# Startgate_Controller-Mainboard.net
KiCad netlist of a schematic drawn in EAGLE
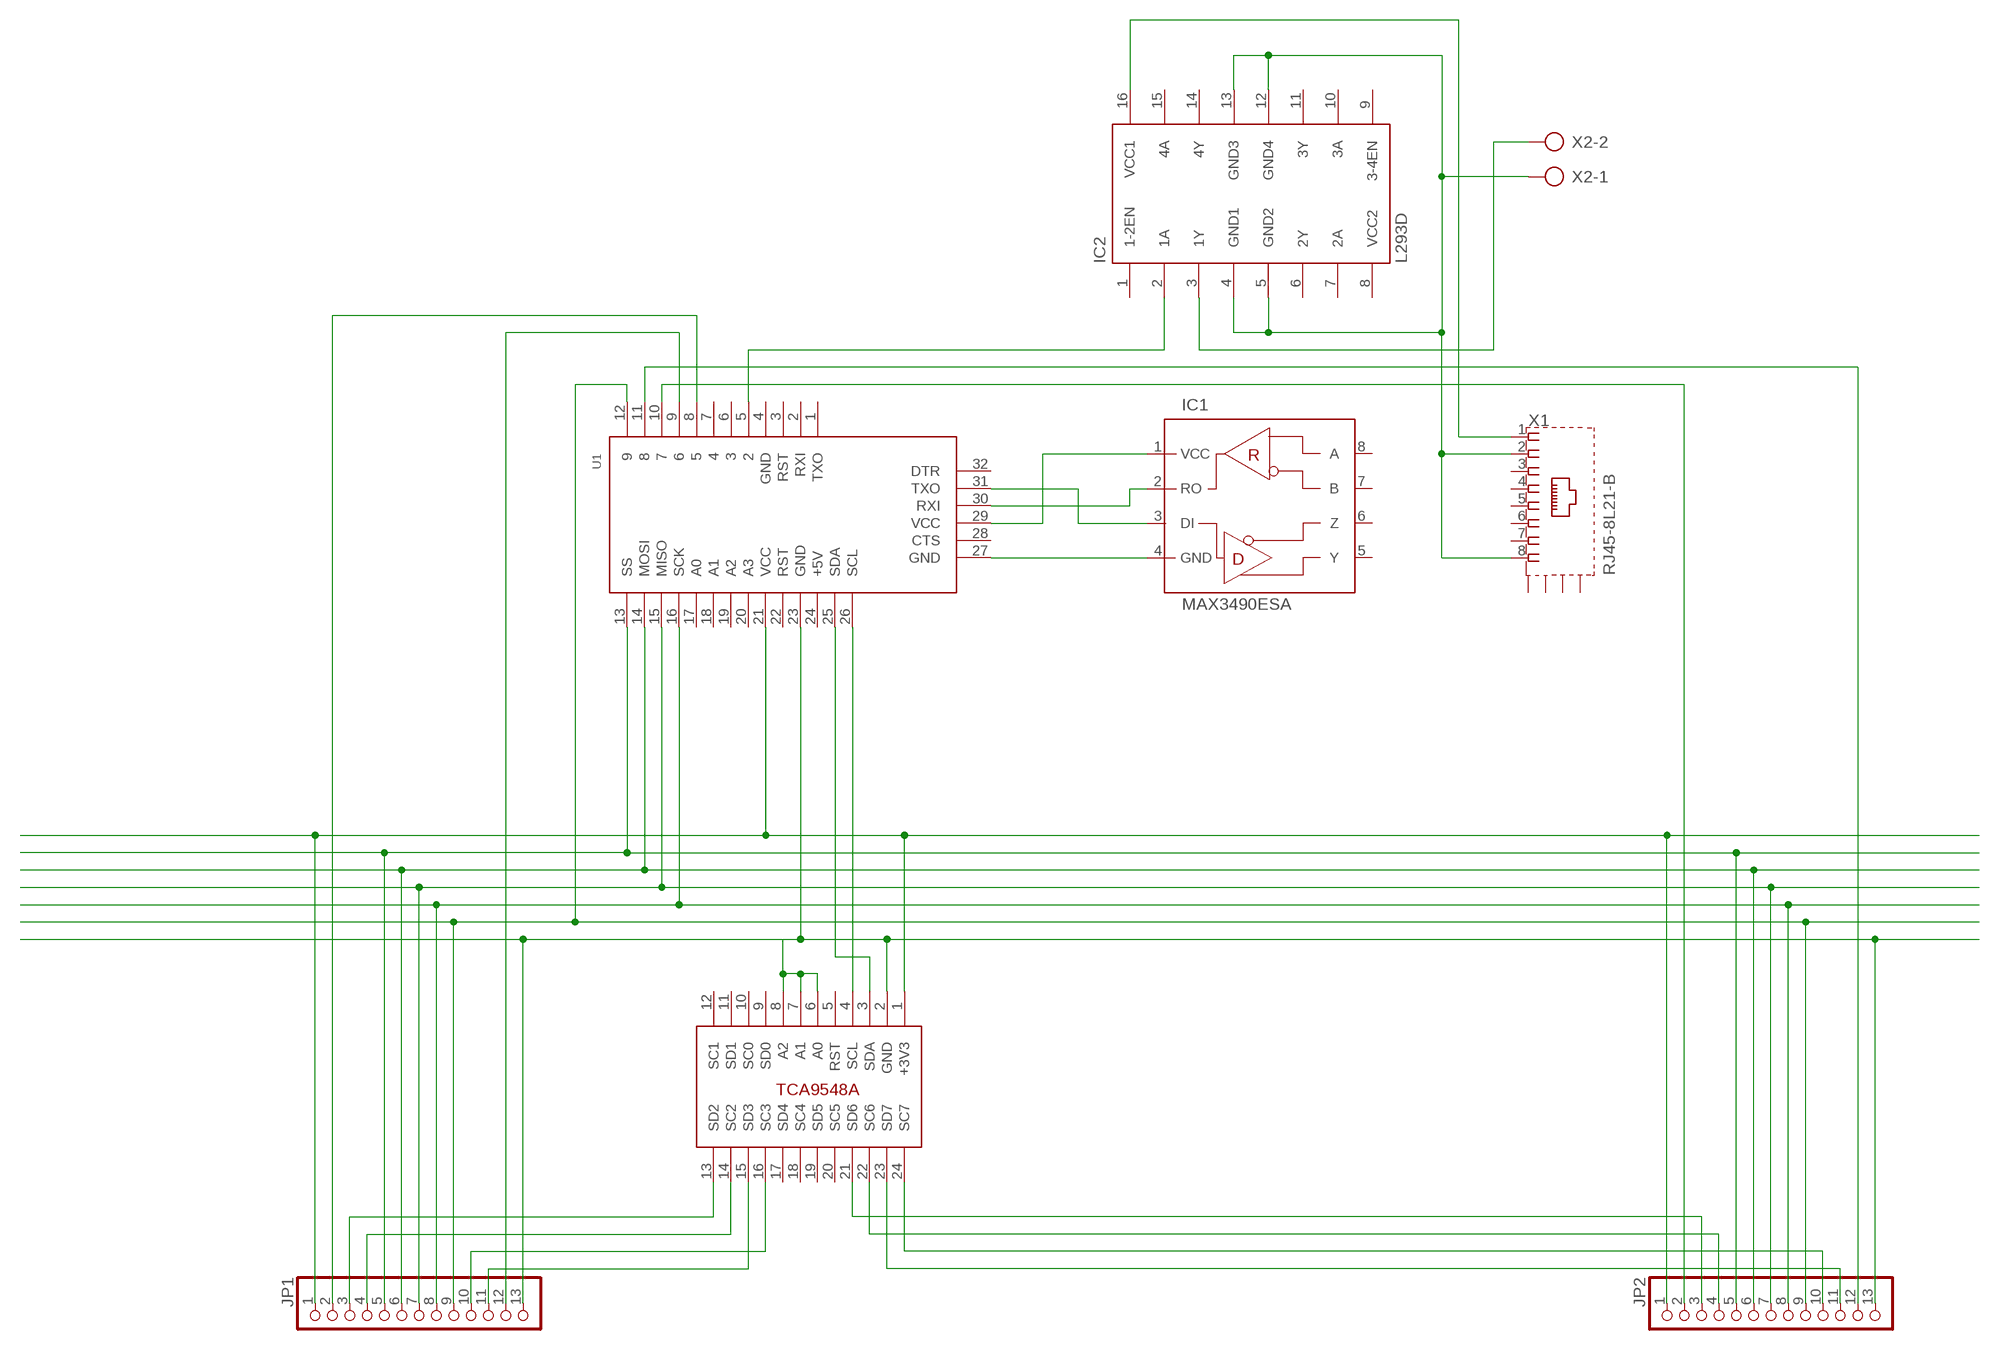
[diagram p0: schematic, sheet 1]

(export (version "E")
  (design (tool "Eeschema 10.0.6"))
  (components
    (comp (ref "IC1")
      (value "MAX3490ESA")
      (footprint "eagle-import:SO08")
      (libsource (lib "eagle-import") (part "MAX3490ESA"))
    )
    (comp (ref "IC2")
      (value "L293D")
      (footprint "eagle-import:DIL16")
      (libsource (lib "eagle-import") (part "L293D"))
    )
    (comp (ref "JP1")
      (value "PINHD-1X13")
      (footprint "eagle-import:1X13")
      (libsource (lib "eagle-import") (part "PINHD-1X13"))
    )
    (comp (ref "JP2")
      (value "PINHD-1X13")
      (footprint "eagle-import:1X13")
      (libsource (lib "eagle-import") (part "PINHD-1X13"))
    )
    (comp (ref "U$1")
      (value "TCA9548A")
      (footprint "eagle-import:DIL24")
      (libsource (lib "eagle-import") (part "TCA9548A"))
    )
    (comp (ref "U1")
      (value "ARDUINOPROMINI")
      (footprint "eagle-import:ARDUINOPROMINI")
      (libsource (lib "eagle-import") (part "ARDUINOPROMINI"))
    )
    (comp (ref "X1")
      (value "RJ45-8L21-B")
      (footprint "eagle-import:RJ45-SHIELD1")
      (libsource (lib "eagle-import") (part "RJ4521-B-8L"))
    )
    (comp (ref "X2")
      (value "AK300/2")
      (footprint "eagle-import:AK300_2")
      (libsource (lib "eagle-import") (part "AK300/2"))
    )
  )
  (nets
    (net (code "1") (name "/+3V3") (class "Default")
      (node (ref "IC1") (pin "1") (pinfunction "VCC_1") (pintype "power_in"))
      (node (ref "JP1") (pin "1") (pinfunction "1_1") (pintype "passive"))
      (node (ref "JP2") (pin "1") (pinfunction "1_1") (pintype "passive"))
      (node (ref "U$1") (pin "1") (pinfunction "+3V3_1") (pintype "power_in"))
      (node (ref "U1") (pin "21") (pinfunction "VCC_21") (pintype "bidirectional"))
      (node (ref "U1") (pin "29") (pinfunction "VCC_29") (pintype "bidirectional"))
    )
    (net (code "2") (name "/+5V") (class "Default")
      (node (ref "U1") (pin "24") (pinfunction "+5V_24") (pintype "power_in"))
    )
    (net (code "3") (name "/GND") (class "Default")
      (node (ref "IC1") (pin "4") (pinfunction "GND_4") (pintype "power_in"))
      (node (ref "JP1") (pin "13") (pinfunction "13_13") (pintype "passive"))
      (node (ref "JP2") (pin "13") (pinfunction "13_13") (pintype "passive"))
      (node (ref "U$1") (pin "2") (pinfunction "GND_2") (pintype "power_in"))
      (node (ref "U$1") (pin "6") (pinfunction "A0_6") (pintype "bidirectional"))
      (node (ref "U$1") (pin "7") (pinfunction "A1_7") (pintype "bidirectional"))
      (node (ref "U$1") (pin "8") (pinfunction "A2_8") (pintype "bidirectional"))
      (node (ref "U1") (pin "23") (pinfunction "GND_23") (pintype "bidirectional"))
      (node (ref "U1") (pin "27") (pinfunction "GND_27") (pintype "bidirectional"))
    )
    (net (code "4") (name "/VCC2") (class "Default")
      (node (ref "IC2") (pin "8") (pinfunction "VCC2_8") (pintype "power_in"))
    )
    (net (code "5") (name "Net-(IC1-DI)") (class "Default")
      (node (ref "IC1") (pin "3") (pinfunction "DI_3") (pintype "input"))
      (node (ref "U1") (pin "31") (pinfunction "TXO_31") (pintype "bidirectional"))
    )
    (net (code "6") (name "Net-(IC1-RO)") (class "Default")
      (node (ref "IC1") (pin "2") (pinfunction "RO_2") (pintype "output"))
      (node (ref "U1") (pin "30") (pinfunction "RXI_30") (pintype "bidirectional"))
    )
    (net (code "7") (name "Net-(IC2-1A)") (class "Default")
      (node (ref "IC2") (pin "2") (pinfunction "1A_2") (pintype "input"))
      (node (ref "U1") (pin "5") (pinfunction "2_5") (pintype "bidirectional"))
    )
    (net (code "8") (name "Net-(IC2-1Y)") (class "Default")
      (node (ref "IC2") (pin "3") (pinfunction "1Y_3") (pintype "output"))
      (node (ref "X2") (pin "2") (pinfunction "KL_2") (pintype "passive"))
    )
    (net (code "9") (name "Net-(IC2-GND1)") (class "Default")
      (node (ref "IC2") (pin "12") (pinfunction "GND4_12") (pintype "power_in"))
      (node (ref "IC2") (pin "13") (pinfunction "GND3_13") (pintype "power_in"))
      (node (ref "IC2") (pin "4") (pinfunction "GND1_4") (pintype "power_in"))
      (node (ref "IC2") (pin "5") (pinfunction "GND2_5") (pintype "power_in"))
      (node (ref "X1") (pin "2") (pinfunction "2_2") (pintype "passive"))
      (node (ref "X1") (pin "8") (pinfunction "8_8") (pintype "passive"))
      (node (ref "X2") (pin "1") (pinfunction "KL_1") (pintype "passive"))
    )
    (net (code "10") (name "Net-(IC2-VCC1)") (class "Default")
      (node (ref "IC2") (pin "16") (pinfunction "VCC1_16") (pintype "power_in"))
      (node (ref "X1") (pin "1") (pinfunction "1_1") (pintype "passive"))
    )
    (net (code "11") (name "Net-(U$1-SC2)") (class "Default")
      (node (ref "JP1") (pin "4") (pinfunction "4_4") (pintype "passive"))
      (node (ref "U$1") (pin "14") (pinfunction "SC2_14") (pintype "bidirectional"))
    )
    (net (code "12") (name "Net-(U$1-SC3)") (class "Default")
      (node (ref "JP1") (pin "10") (pinfunction "10_10") (pintype "passive"))
      (node (ref "U$1") (pin "16") (pinfunction "SC3_16") (pintype "bidirectional"))
    )
    (net (code "13") (name "Net-(U$1-SC6)") (class "Default")
      (node (ref "JP2") (pin "4") (pinfunction "4_4") (pintype "passive"))
      (node (ref "U$1") (pin "22") (pinfunction "SC6_22") (pintype "bidirectional"))
    )
    (net (code "14") (name "Net-(U$1-SC7)") (class "Default")
      (node (ref "JP2") (pin "10") (pinfunction "10_10") (pintype "passive"))
      (node (ref "U$1") (pin "24") (pinfunction "SC7_24") (pintype "bidirectional"))
    )
    (net (code "15") (name "Net-(U$1-SCL)") (class "Default")
      (node (ref "U$1") (pin "4") (pinfunction "SCL_4") (pintype "bidirectional"))
      (node (ref "U1") (pin "26") (pinfunction "SCL_26") (pintype "bidirectional"))
    )
    (net (code "16") (name "Net-(U$1-SD2)") (class "Default")
      (node (ref "JP1") (pin "3") (pinfunction "3_3") (pintype "passive"))
      (node (ref "U$1") (pin "13") (pinfunction "SD2_13") (pintype "bidirectional"))
    )
    (net (code "17") (name "Net-(U$1-SD3)") (class "Default")
      (node (ref "JP1") (pin "11") (pinfunction "11_11") (pintype "passive"))
      (node (ref "U$1") (pin "15") (pinfunction "SD3_15") (pintype "bidirectional"))
    )
    (net (code "18") (name "Net-(U$1-SD6)") (class "Default")
      (node (ref "JP2") (pin "3") (pinfunction "3_3") (pintype "passive"))
      (node (ref "U$1") (pin "21") (pinfunction "SD6_21") (pintype "bidirectional"))
    )
    (net (code "19") (name "Net-(U$1-SD7)") (class "Default")
      (node (ref "JP2") (pin "11") (pinfunction "11_11") (pintype "passive"))
      (node (ref "U$1") (pin "23") (pinfunction "SD7_23") (pintype "bidirectional"))
    )
    (net (code "20") (name "Net-(U$1-SDA)") (class "Default")
      (node (ref "U$1") (pin "3") (pinfunction "SDA_3") (pintype "bidirectional"))
      (node (ref "U1") (pin "25") (pinfunction "SDA_25") (pintype "bidirectional"))
    )
    (net (code "21") (name "Net-(U1-5)") (class "Default")
      (node (ref "JP1") (pin "2") (pinfunction "2_2") (pintype "passive"))
      (node (ref "U1") (pin "8") (pinfunction "5_8") (pintype "bidirectional"))
    )
    (net (code "22") (name "Net-(U1-6)") (class "Default")
      (node (ref "JP1") (pin "12") (pinfunction "12_12") (pintype "passive"))
      (node (ref "U1") (pin "9") (pinfunction "6_9") (pintype "bidirectional"))
    )
    (net (code "23") (name "Net-(U1-7)") (class "Default")
      (node (ref "JP2") (pin "2") (pinfunction "2_2") (pintype "passive"))
      (node (ref "U1") (pin "10") (pinfunction "7_10") (pintype "bidirectional"))
    )
    (net (code "24") (name "Net-(U1-8)") (class "Default")
      (node (ref "JP2") (pin "12") (pinfunction "12_12") (pintype "passive"))
      (node (ref "U1") (pin "11") (pinfunction "8_11") (pintype "bidirectional"))
    )
    (net (code "25") (name "Net-(U1-9)") (class "Default")
      (node (ref "JP1") (pin "9") (pinfunction "9_9") (pintype "passive"))
      (node (ref "JP2") (pin "9") (pinfunction "9_9") (pintype "passive"))
      (node (ref "U1") (pin "12") (pinfunction "9_12") (pintype "bidirectional"))
    )
    (net (code "26") (name "Net-(U1-MISO)") (class "Default")
      (node (ref "JP1") (pin "7") (pinfunction "7_7") (pintype "passive"))
      (node (ref "JP2") (pin "7") (pinfunction "7_7") (pintype "passive"))
      (node (ref "U1") (pin "15") (pinfunction "MISO_15") (pintype "bidirectional"))
    )
    (net (code "27") (name "Net-(U1-MOSI)") (class "Default")
      (node (ref "JP1") (pin "6") (pinfunction "6_6") (pintype "passive"))
      (node (ref "JP2") (pin "6") (pinfunction "6_6") (pintype "passive"))
      (node (ref "U1") (pin "14") (pinfunction "MOSI_14") (pintype "bidirectional"))
    )
    (net (code "28") (name "Net-(U1-SCK)") (class "Default")
      (node (ref "JP1") (pin "8") (pinfunction "8_8") (pintype "passive"))
      (node (ref "JP2") (pin "8") (pinfunction "8_8") (pintype "passive"))
      (node (ref "U1") (pin "16") (pinfunction "SCK_16") (pintype "bidirectional"))
    )
    (net (code "29") (name "Net-(U1-SS)") (class "Default")
      (node (ref "JP1") (pin "5") (pinfunction "5_5") (pintype "passive"))
      (node (ref "JP2") (pin "5") (pinfunction "5_5") (pintype "passive"))
      (node (ref "U1") (pin "13") (pinfunction "SS_13") (pintype "bidirectional"))
    )
    (net (code "30") (name "unconnected-(IC1-A-Pad8)") (class "Default")
      (node (ref "IC1") (pin "8") (pinfunction "A_8") (pintype "input"))
    )
    (net (code "31") (name "unconnected-(IC1-B-Pad7)") (class "Default")
      (node (ref "IC1") (pin "7") (pinfunction "B_7") (pintype "input"))
    )
    (net (code "32") (name "unconnected-(IC1-Y-Pad5)") (class "Default")
      (node (ref "IC1") (pin "5") (pinfunction "Y_5") (pintype "output"))
    )
    (net (code "33") (name "unconnected-(IC1-Z-Pad6)") (class "Default")
      (node (ref "IC1") (pin "6") (pinfunction "Z_6") (pintype "output"))
    )
    (net (code "34") (name "unconnected-(IC2-1-2EN-Pad1)") (class "Default")
      (node (ref "IC2") (pin "1") (pinfunction "1-2EN_1") (pintype "input"))
    )
    (net (code "35") (name "unconnected-(IC2-2A-Pad7)") (class "Default")
      (node (ref "IC2") (pin "7") (pinfunction "2A_7") (pintype "input"))
    )
    (net (code "36") (name "unconnected-(IC2-2Y-Pad6)") (class "Default")
      (node (ref "IC2") (pin "6") (pinfunction "2Y_6") (pintype "output"))
    )
    (net (code "37") (name "unconnected-(IC2-3-4EN-Pad9)") (class "Default")
      (node (ref "IC2") (pin "9") (pinfunction "3-4EN_9") (pintype "input"))
    )
    (net (code "38") (name "unconnected-(IC2-3A-Pad10)") (class "Default")
      (node (ref "IC2") (pin "10") (pinfunction "3A_10") (pintype "input"))
    )
    (net (code "39") (name "unconnected-(IC2-3Y-Pad11)") (class "Default")
      (node (ref "IC2") (pin "11") (pinfunction "3Y_11") (pintype "output"))
    )
    (net (code "40") (name "unconnected-(IC2-4A-Pad15)") (class "Default")
      (node (ref "IC2") (pin "15") (pinfunction "4A_15") (pintype "input"))
    )
    (net (code "41") (name "unconnected-(IC2-4Y-Pad14)") (class "Default")
      (node (ref "IC2") (pin "14") (pinfunction "4Y_14") (pintype "output"))
    )
    (net (code "42") (name "unconnected-(U$1-RST-Pad5)") (class "Default")
      (node (ref "U$1") (pin "5") (pinfunction "RST_5") (pintype "bidirectional"))
    )
    (net (code "43") (name "unconnected-(U$1-SC0-Pad10)") (class "Default")
      (node (ref "U$1") (pin "10") (pinfunction "SC0_10") (pintype "bidirectional"))
    )
    (net (code "44") (name "unconnected-(U$1-SC1-Pad12)") (class "Default")
      (node (ref "U$1") (pin "12") (pinfunction "SC1_12") (pintype "bidirectional"))
    )
    (net (code "45") (name "unconnected-(U$1-SC4-Pad18)") (class "Default")
      (node (ref "U$1") (pin "18") (pinfunction "SC4_18") (pintype "bidirectional"))
    )
    (net (code "46") (name "unconnected-(U$1-SC5-Pad20)") (class "Default")
      (node (ref "U$1") (pin "20") (pinfunction "SC5_20") (pintype "bidirectional"))
    )
    (net (code "47") (name "unconnected-(U$1-SD0-Pad9)") (class "Default")
      (node (ref "U$1") (pin "9") (pinfunction "SD0_9") (pintype "bidirectional"))
    )
    (net (code "48") (name "unconnected-(U$1-SD1-Pad11)") (class "Default")
      (node (ref "U$1") (pin "11") (pinfunction "SD1_11") (pintype "bidirectional"))
    )
    (net (code "49") (name "unconnected-(U$1-SD4-Pad17)") (class "Default")
      (node (ref "U$1") (pin "17") (pinfunction "SD4_17") (pintype "bidirectional"))
    )
    (net (code "50") (name "unconnected-(U$1-SD5-Pad19)") (class "Default")
      (node (ref "U$1") (pin "19") (pinfunction "SD5_19") (pintype "bidirectional"))
    )
    (net (code "51") (name "unconnected-(U1-3-Pad6)") (class "Default")
      (node (ref "U1") (pin "6") (pinfunction "3_6") (pintype "bidirectional"))
    )
    (net (code "52") (name "unconnected-(U1-4-Pad7)") (class "Default")
      (node (ref "U1") (pin "7") (pinfunction "4_7") (pintype "bidirectional"))
    )
    (net (code "53") (name "unconnected-(U1-A0-Pad17)") (class "Default")
      (node (ref "U1") (pin "17") (pinfunction "A0_17") (pintype "bidirectional"))
    )
    (net (code "54") (name "unconnected-(U1-A1-Pad18)") (class "Default")
      (node (ref "U1") (pin "18") (pinfunction "A1_18") (pintype "bidirectional"))
    )
    (net (code "55") (name "unconnected-(U1-A2-Pad19)") (class "Default")
      (node (ref "U1") (pin "19") (pinfunction "A2_19") (pintype "bidirectional"))
    )
    (net (code "56") (name "unconnected-(U1-A3-Pad20)") (class "Default")
      (node (ref "U1") (pin "20") (pinfunction "A3_20") (pintype "bidirectional"))
    )
    (net (code "57") (name "unconnected-(U1-CTS-Pad28)") (class "Default")
      (node (ref "U1") (pin "28") (pinfunction "CTS_28") (pintype "bidirectional"))
    )
    (net (code "58") (name "unconnected-(U1-DTR-Pad32)") (class "Default")
      (node (ref "U1") (pin "32") (pinfunction "DTR_32") (pintype "bidirectional"))
    )
    (net (code "59") (name "unconnected-(U1-GND-Pad4)") (class "Default")
      (node (ref "U1") (pin "4") (pinfunction "GND_4") (pintype "bidirectional"))
    )
    (net (code "60") (name "unconnected-(U1-RST-Pad3)") (class "Default")
      (node (ref "U1") (pin "3") (pinfunction "RST_3") (pintype "bidirectional"))
    )
    (net (code "61") (name "unconnected-(U1-RST-Pad22)") (class "Default")
      (node (ref "U1") (pin "22") (pinfunction "RST_22") (pintype "bidirectional"))
    )
    (net (code "62") (name "unconnected-(U1-RXI-Pad2)") (class "Default")
      (node (ref "U1") (pin "2") (pinfunction "RXI_2") (pintype "bidirectional"))
    )
    (net (code "63") (name "unconnected-(U1-TXO-Pad1)") (class "Default")
      (node (ref "U1") (pin "1") (pinfunction "TXO_1") (pintype "bidirectional"))
    )
    (net (code "64") (name "unconnected-(X1-Pad3)") (class "Default")
      (node (ref "X1") (pin "3") (pinfunction "3_3") (pintype "passive"))
    )
    (net (code "65") (name "unconnected-(X1-Pad4)") (class "Default")
      (node (ref "X1") (pin "4") (pinfunction "4_4") (pintype "passive"))
    )
    (net (code "66") (name "unconnected-(X1-Pad5)") (class "Default")
      (node (ref "X1") (pin "5") (pinfunction "5_5") (pintype "passive"))
    )
    (net (code "67") (name "unconnected-(X1-Pad6)") (class "Default")
      (node (ref "X1") (pin "6") (pinfunction "6_6") (pintype "passive"))
    )
    (net (code "68") (name "unconnected-(X1-Pad7)") (class "Default")
      (node (ref "X1") (pin "7") (pinfunction "7_7") (pintype "passive"))
    )
    (net (code "69") (name "unconnected-(X1-S-PadS1)") (class "Default")
      (node (ref "X1") (pin "S1") (pinfunction "S_S1") (pintype "passive"))
    )
    (net (code "70") (name "unconnected-(X1-S-PadS2)") (class "Default")
      (node (ref "X1") (pin "S2") (pinfunction "S_S2") (pintype "passive"))
    )
    (net (code "71") (name "unconnected-(X1-S-PadS3)") (class "Default")
      (node (ref "X1") (pin "S3") (pinfunction "S_S3") (pintype "passive"))
    )
    (net (code "72") (name "unconnected-(X1-S-PadS4)") (class "Default")
      (node (ref "X1") (pin "S4") (pinfunction "S_S4") (pintype "passive"))
    )
  )
)
